# 38kHzSensorRevB1.net
KiCad netlist of a schematic drawn in EAGLE
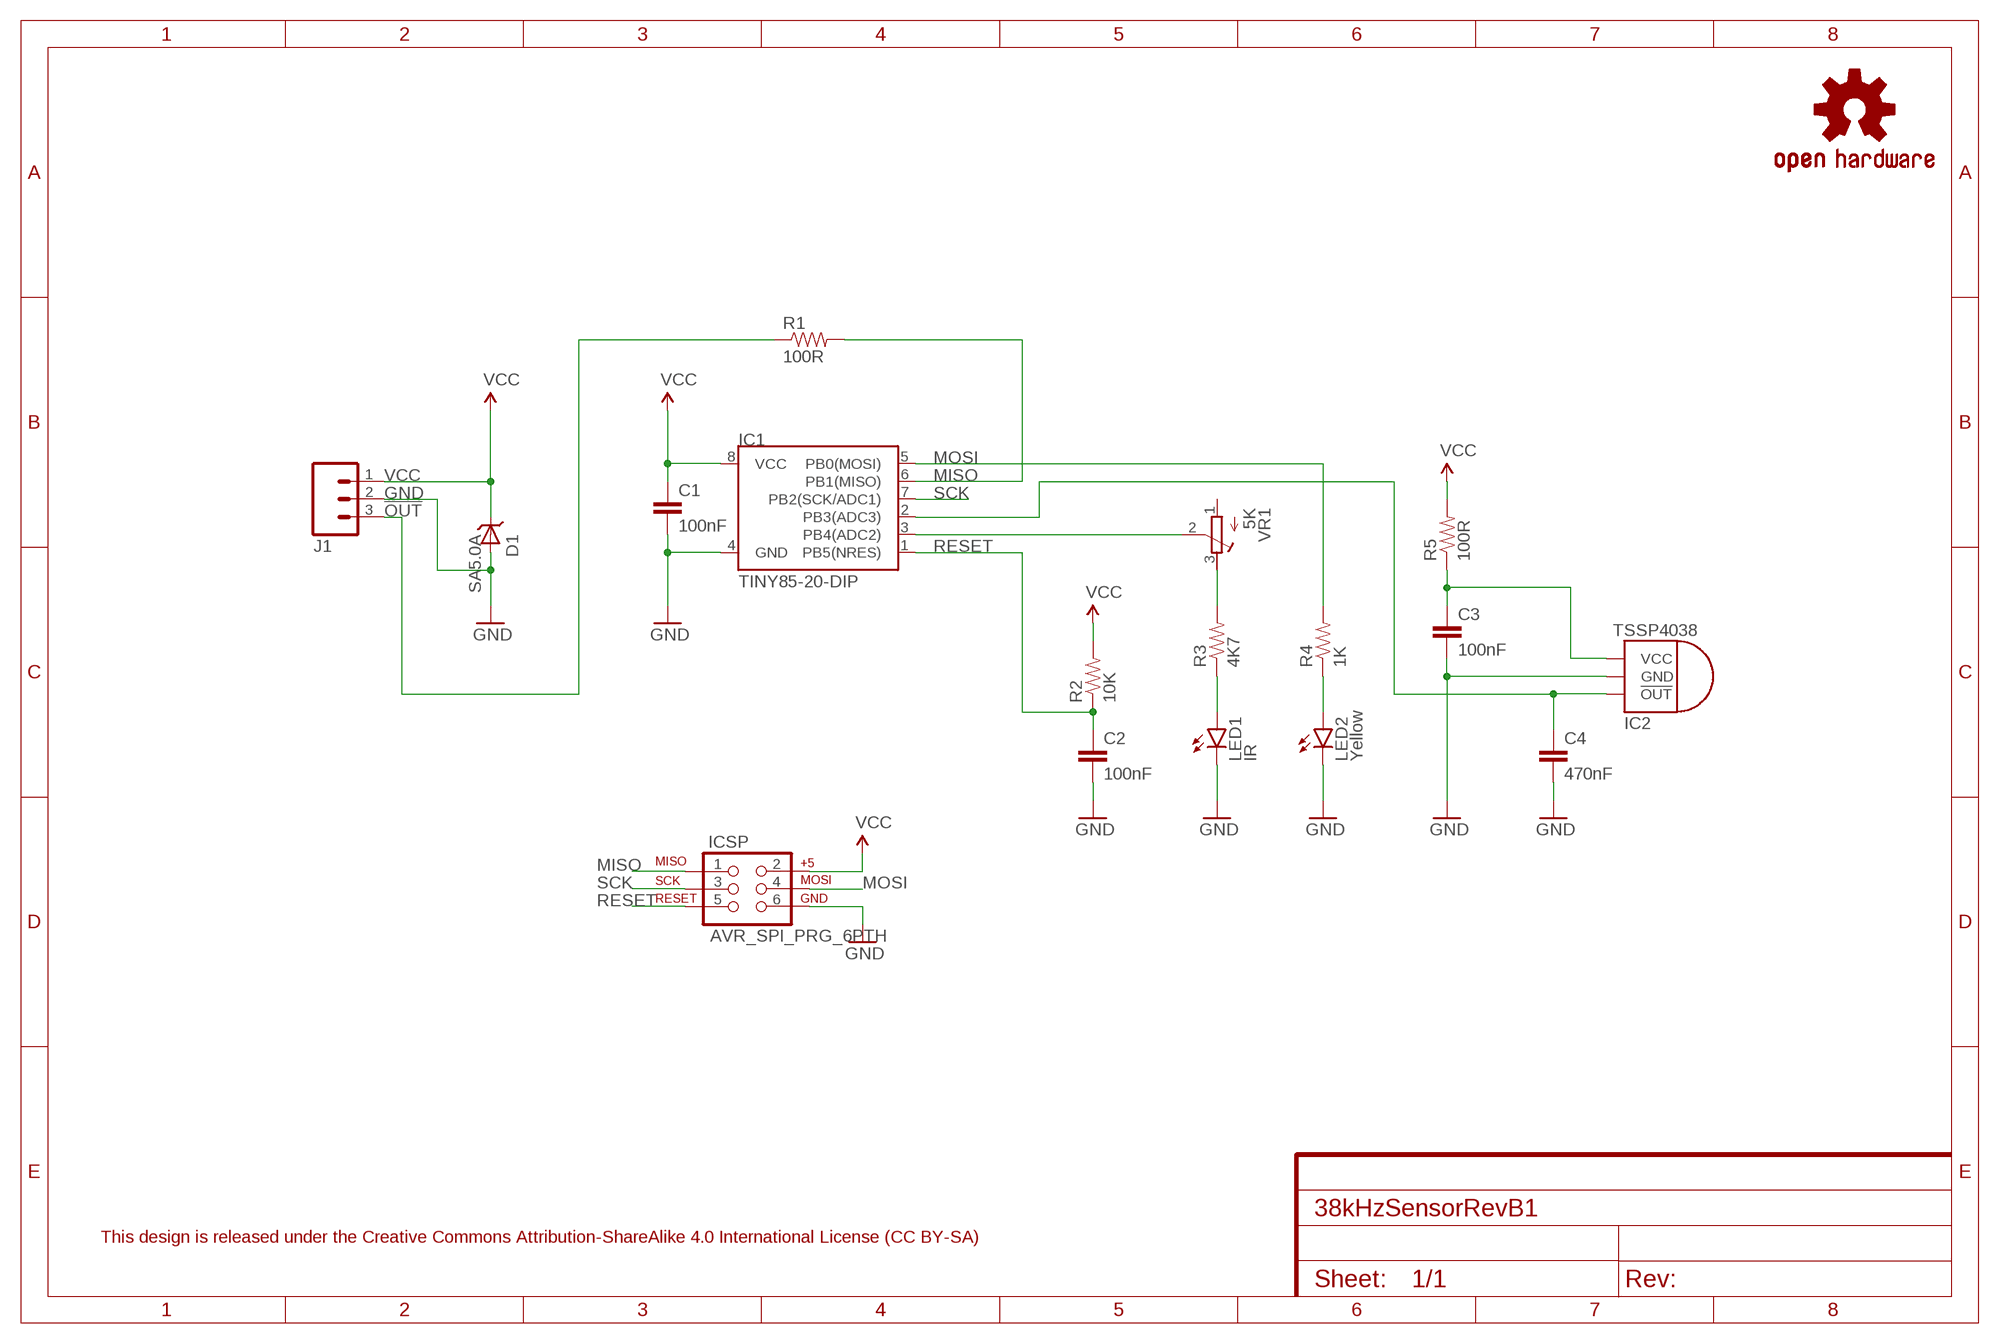
[diagram p0: schematic, sheet 1]

(export (version "E")
  (design (tool "Eeschema 10.0.6"))
  (components
    (comp (ref "C1")
      (value "100nF")
      (footprint "eagle-import:CAP-PTH-SMALL")
      (libsource (lib "eagle-import") (part "CAPPTH"))
    )
    (comp (ref "C2")
      (value "100nF")
      (footprint "eagle-import:CAP-PTH-SMALL")
      (libsource (lib "eagle-import") (part "CAPPTH"))
    )
    (comp (ref "C3")
      (value "100nF")
      (footprint "eagle-import:CAP-PTH-SMALL")
      (libsource (lib "eagle-import") (part "CAPPTH"))
    )
    (comp (ref "C4")
      (value "470nF")
      (footprint "eagle-import:CAP-PTH-5MM")
      (libsource (lib "eagle-import") (part "CAPPTH1"))
    )
    (comp (ref "D1")
      (value "SA5.0A")
      (footprint "eagle-import:DO41_TVS_UNI")
      (libsource (lib "eagle-import") (part "SA5.0A"))
    )
    (comp (ref "IC1")
      (value "TINY85-20-DIP")
      (footprint "eagle-import:DIP08")
      (libsource (lib "eagle-import") (part "ATTINY45TINY85-20-DIP"))
    )
    (comp (ref "IC2")
      (value "TSSP4038EDGE")
      (footprint "eagle-import:TSSP4038_PKG_EDGE")
      (libsource (lib "eagle-import") (part "TSSP4038EDGE"))
    )
    (comp (ref "ICSP")
      (value "AVR_SPI_PRG_6PTH")
      (footprint "eagle-import:2X3")
      (libsource (lib "eagle-import") (part "AVR_SPI_PRG_6PTH"))
    )
    (comp (ref "J1")
      (value "M03PTH")
      (footprint "eagle-import:1X03")
      (libsource (lib "eagle-import") (part "M03PTH"))
    )
    (comp (ref "LED1")
      (value "IR")
      (footprint "eagle-import:LED5MM")
      (libsource (lib "eagle-import") (part "LED5MM"))
    )
    (comp (ref "LED2")
      (value "Yellow")
      (footprint "eagle-import:LED3MM")
      (libsource (lib "eagle-import") (part "LED3MM"))
    )
    (comp (ref "LOGO1")
      (value "OSHW-LOGOS")
      (footprint "eagle-import:OSHW-LOGO-S")
      (libsource (lib "eagle-import") (part "OSHW-LOGOS"))
    )
    (comp (ref "R1")
      (value "100R")
      (footprint "eagle-import:AXIAL-0.4")
      (libsource (lib "eagle-import") (part "RESISTORPTH-1/4W"))
    )
    (comp (ref "R2")
      (value "10K")
      (footprint "eagle-import:AXIAL-0.4")
      (libsource (lib "eagle-import") (part "RESISTORPTH-1/4W"))
    )
    (comp (ref "R3")
      (value "4K7")
      (footprint "eagle-import:AXIAL-0.4")
      (libsource (lib "eagle-import") (part "RESISTORPTH-1/4W"))
    )
    (comp (ref "R4")
      (value "1K")
      (footprint "eagle-import:AXIAL-0.4")
      (libsource (lib "eagle-import") (part "RESISTORPTH-1/4W"))
    )
    (comp (ref "R5")
      (value "100R")
      (footprint "eagle-import:AXIAL-0.4")
      (libsource (lib "eagle-import") (part "RESISTORPTH-1/4W"))
    )
    (comp (ref "VR1")
      (value "5K")
      (footprint "eagle-import:RTRIM3296X")
      (libsource (lib "eagle-import") (part "R-TRIMM3296X"))
    )
  )
  (nets
    (net (code "1") (name "/MISO") (class "Default")
      (node (ref "IC1") (pin "6") (pinfunction "PB1(MISO)_6") (pintype "bidirectional"))
      (node (ref "ICSP") (pin "1") (pinfunction "1_1") (pintype "passive"))
      (node (ref "R1") (pin "P$2") (pinfunction "2_P$2") (pintype "passive"))
    )
    (net (code "2") (name "/MOSI") (class "Default")
      (node (ref "IC1") (pin "5") (pinfunction "PB0(MOSI)_5") (pintype "bidirectional"))
      (node (ref "ICSP") (pin "4") (pinfunction "4_4") (pintype "passive"))
      (node (ref "R4") (pin "P$2") (pinfunction "2_P$2") (pintype "passive"))
    )
    (net (code "3") (name "/RESET") (class "Default")
      (node (ref "C2") (pin "1") (pinfunction "1_1") (pintype "passive"))
      (node (ref "IC1") (pin "1") (pinfunction "PB5(NRES)_1") (pintype "bidirectional"))
      (node (ref "ICSP") (pin "5") (pinfunction "5_5") (pintype "passive"))
      (node (ref "R2") (pin "P$1") (pinfunction "1_P$1") (pintype "passive"))
    )
    (net (code "4") (name "/SCK") (class "Default")
      (node (ref "IC1") (pin "7") (pinfunction "PB2(SCK/ADC1)_7") (pintype "bidirectional"))
      (node (ref "ICSP") (pin "3") (pinfunction "3_3") (pintype "passive"))
    )
    (net (code "5") (name "/~{OUT}") (class "Default")
      (node (ref "J1") (pin "3") (pinfunction "3_3") (pintype "passive"))
      (node (ref "R1") (pin "P$1") (pinfunction "1_P$1") (pintype "passive"))
    )
    (net (code "6") (name "GND") (class "Default")
      (node (ref "C1") (pin "2") (pinfunction "2_2") (pintype "passive"))
      (node (ref "C2") (pin "2") (pinfunction "2_2") (pintype "passive"))
      (node (ref "C3") (pin "2") (pinfunction "2_2") (pintype "passive"))
      (node (ref "C4") (pin "2") (pinfunction "2_2") (pintype "passive"))
      (node (ref "D1") (pin "ANODE") (pinfunction "ANODE_ANODE") (pintype "passive"))
      (node (ref "IC1") (pin "4") (pinfunction "GND_4") (pintype "bidirectional"))
      (node (ref "IC2") (pin "GND") (pinfunction "GND_GND") (pintype "bidirectional"))
      (node (ref "ICSP") (pin "6") (pinfunction "6_6") (pintype "passive"))
      (node (ref "J1") (pin "2") (pinfunction "2_2") (pintype "passive"))
      (node (ref "LED1") (pin "K") (pinfunction "C_K") (pintype "passive"))
      (node (ref "LED2") (pin "K") (pinfunction "C_K") (pintype "passive"))
    )
    (net (code "7") (name "Net-(IC1-PB3(ADC3))") (class "Default")
      (node (ref "C4") (pin "1") (pinfunction "1_1") (pintype "passive"))
      (node (ref "IC1") (pin "2") (pinfunction "PB3(ADC3)_2") (pintype "bidirectional"))
      (node (ref "IC2") (pin "OUT") (pinfunction "~{OUT}_OUT") (pintype "bidirectional"))
    )
    (net (code "8") (name "Net-(IC1-PB4(ADC2))") (class "Default")
      (node (ref "IC1") (pin "3") (pinfunction "PB4(ADC2)_3") (pintype "bidirectional"))
      (node (ref "VR1") (pin "2") (pinfunction "S_2") (pintype "passive"))
    )
    (net (code "9") (name "Net-(R3-1)") (class "Default")
      (node (ref "LED1") (pin "A") (pinfunction "A_A") (pintype "passive"))
      (node (ref "R3") (pin "P$1") (pinfunction "1_P$1") (pintype "passive"))
    )
    (net (code "10") (name "Net-(R3-2)") (class "Default")
      (node (ref "R3") (pin "P$2") (pinfunction "2_P$2") (pintype "passive"))
      (node (ref "VR1") (pin "3") (pinfunction "E_3") (pintype "passive"))
    )
    (net (code "11") (name "Net-(R4-1)") (class "Default")
      (node (ref "LED2") (pin "A") (pinfunction "A_A") (pintype "passive"))
      (node (ref "R4") (pin "P$1") (pinfunction "1_P$1") (pintype "passive"))
    )
    (net (code "12") (name "Net-(R5-1)") (class "Default")
      (node (ref "C3") (pin "1") (pinfunction "1_1") (pintype "passive"))
      (node (ref "IC2") (pin "VCC") (pinfunction "VCC_VCC") (pintype "bidirectional"))
      (node (ref "R5") (pin "P$1") (pinfunction "1_P$1") (pintype "passive"))
    )
    (net (code "13") (name "VCC") (class "Default")
      (node (ref "C1") (pin "1") (pinfunction "1_1") (pintype "passive"))
      (node (ref "D1") (pin "CATHODE") (pinfunction "CATHODE_CATHODE") (pintype "passive"))
      (node (ref "IC1") (pin "8") (pinfunction "VCC_8") (pintype "bidirectional"))
      (node (ref "ICSP") (pin "2") (pinfunction "2_2") (pintype "passive"))
      (node (ref "J1") (pin "1") (pinfunction "1_1") (pintype "passive"))
      (node (ref "R2") (pin "P$2") (pinfunction "2_P$2") (pintype "passive"))
      (node (ref "R5") (pin "P$2") (pinfunction "2_P$2") (pintype "passive"))
    )
    (net (code "14") (name "unconnected-(VR1-A-Pad1)") (class "Default")
      (node (ref "VR1") (pin "1") (pinfunction "A_1") (pintype "passive"))
    )
  )
)
